# board.net
KiCad netlist of a schematic drawn in EAGLE
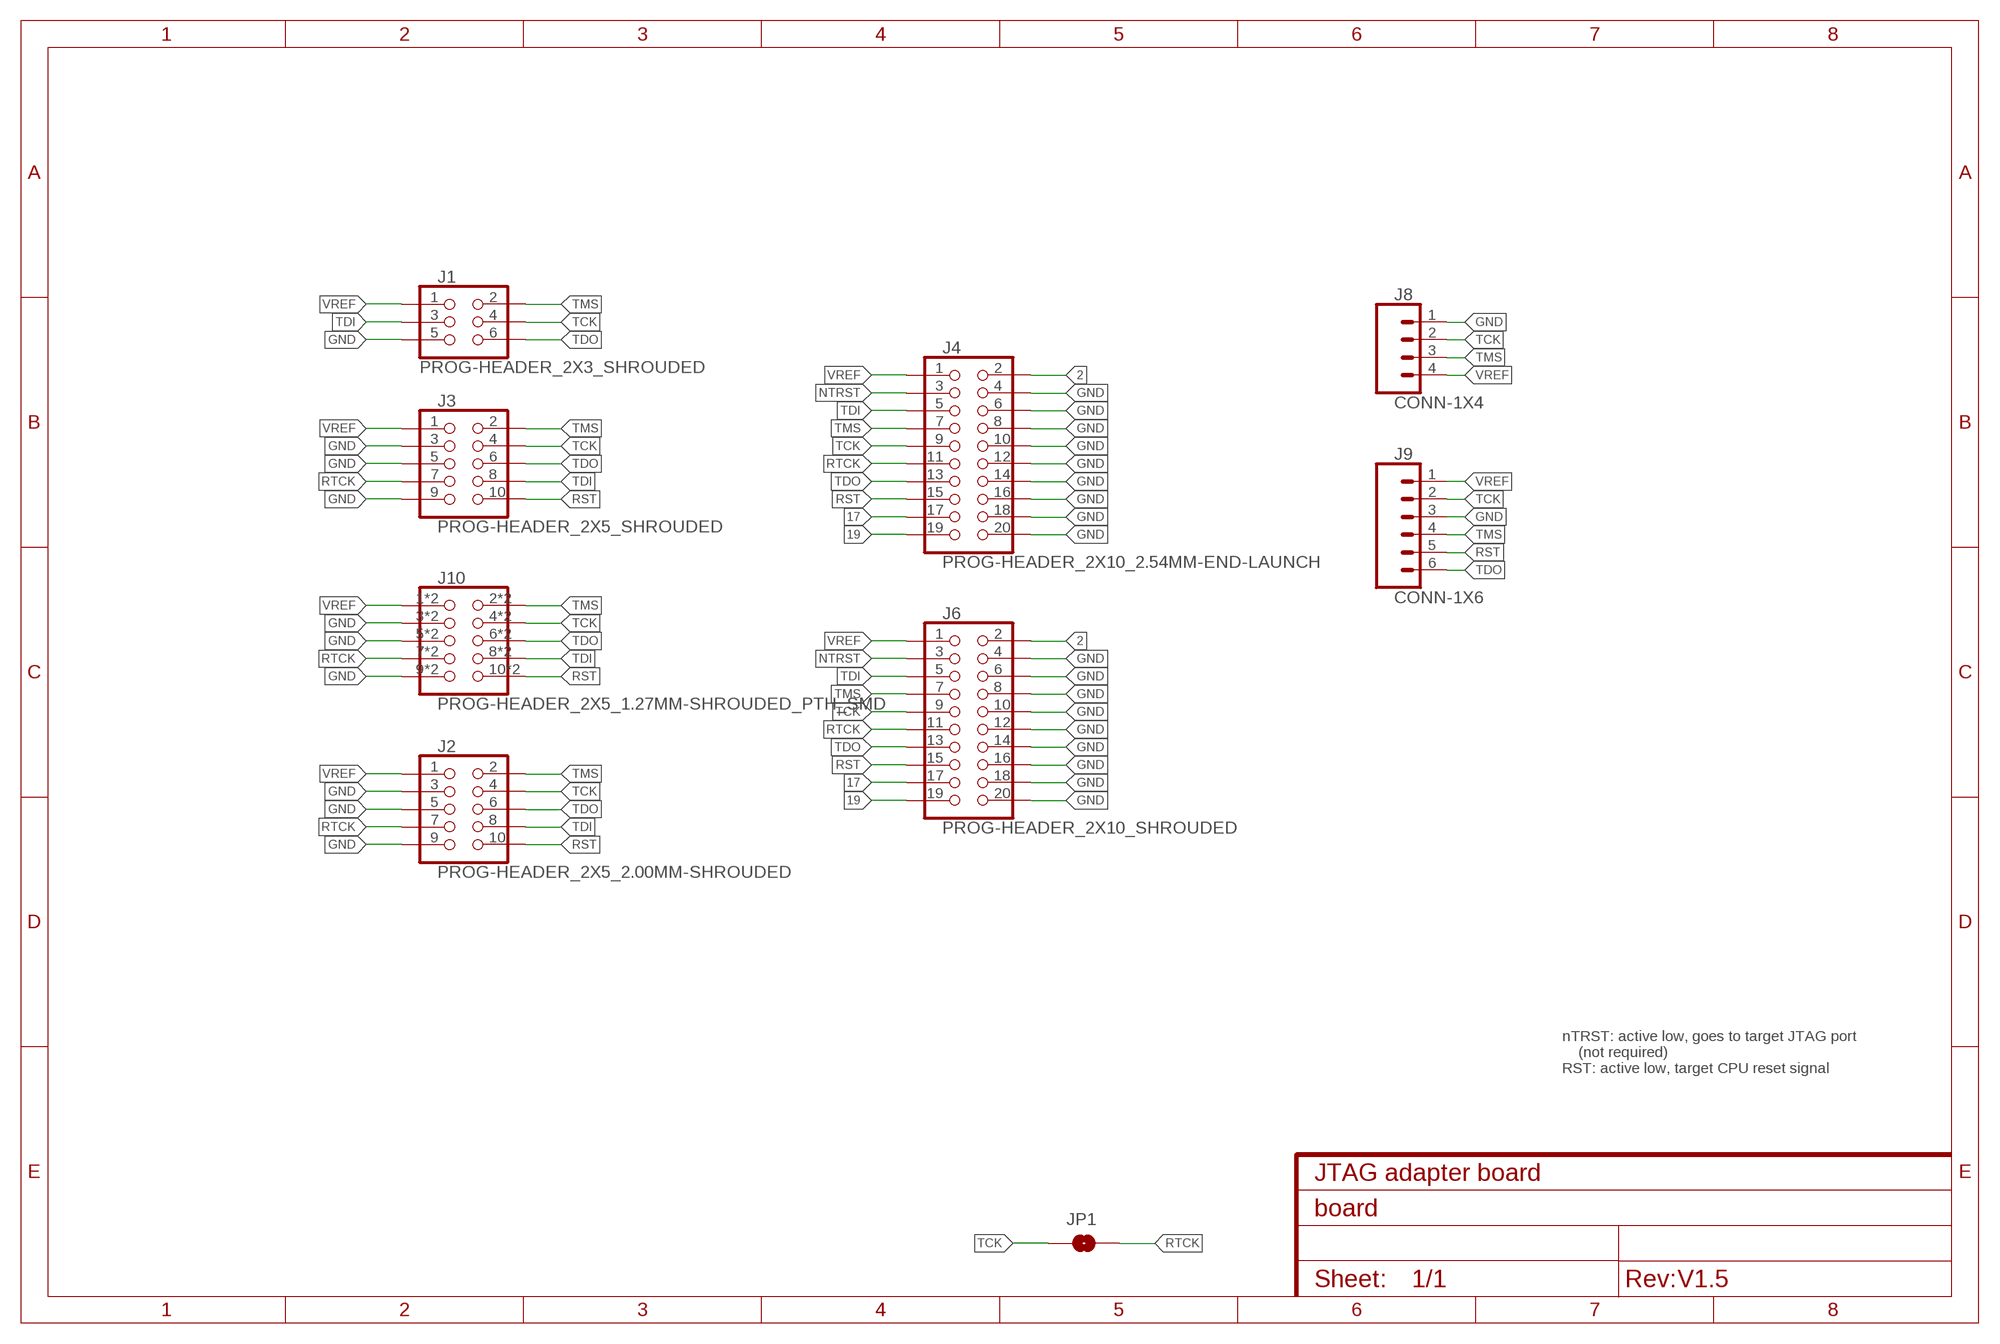
[diagram p0: schematic, sheet 1]

(export (version "E")
  (design (tool "Eeschema 10.0.6"))
  (components
    (comp (ref "J1")
      (value "PROG-HEADER_2X3_SHROUDED")
      (footprint "eagle-import:2X3-2.54MM-SHROUDED")
      (libsource (lib "eagle-import") (part "PROG-HEADER_2X3_SHROUDED"))
    )
    (comp (ref "J2")
      (value "PROG-HEADER_2X5_2.00MM-SHROUDED")
      (footprint "eagle-import:2X5-2.00MM-SHROUDED")
      (libsource (lib "eagle-import") (part "PROG-HEADER_2X5_2.00MM-SHROUDED"))
    )
    (comp (ref "J3")
      (value "PROG-HEADER_2X5_SHROUDED")
      (footprint "eagle-import:2X5-2.54MM-SHROUDED")
      (libsource (lib "eagle-import") (part "PROG-HEADER_2X5_SHROUDED"))
    )
    (comp (ref "J4")
      (value "PROG-HEADER_2X10_2.54MM-END-LAUNCH")
      (footprint "eagle-import:2X10-2.54MM-END-LAUNCH")
      (libsource (lib "eagle-import") (part "PROG-HEADER_2X10_2.54MM-END-LAUNCH"))
    )
    (comp (ref "J6")
      (value "PROG-HEADER_2X10_SHROUDED")
      (footprint "eagle-import:2X10-2.54MM-SHROUDED")
      (libsource (lib "eagle-import") (part "PROG-HEADER_2X10_SHROUDED"))
    )
    (comp (ref "J8")
      (value "CONN-1X4")
      (footprint "eagle-import:MOLEX-1X4-2.54MM")
      (libsource (lib "eagle-import") (part "CONN-1X4"))
    )
    (comp (ref "J9")
      (value "CONN-1X6")
      (footprint "eagle-import:MOLEX-1X6-2.54MM")
      (libsource (lib "eagle-import") (part "CONN-1X6"))
    )
    (comp (ref "J10")
      (value "PROG-HEADER_2X5_1.27MM-SHROUDED_PTH_SMD")
      (footprint "eagle-import:2X5-1.27MM-SHROUDED_PTH+SMD")
      (libsource (lib "eagle-import") (part "PROG-HEADER_2X5_1.27MM-SHROUDED_PTH_SMD"))
    )
    (comp (ref "JP1")
      (value "TCK-RTCK")
      (footprint "eagle-import:SMT-JUMPER_2_NO_SILK")
      (libsource (lib "eagle-import") (part "JUMPER-SMT_2_NO_SILK"))
    )
  )
  (nets
    (net (code "1") (name "2") (class "Default")
      (node (ref "J4") (pin "2") (pinfunction "2_2") (pintype "power_in"))
      (node (ref "J6") (pin "2") (pinfunction "2_2") (pintype "power_in"))
    )
    (net (code "2") (name "17") (class "Default")
      (node (ref "J4") (pin "17") (pinfunction "17_17") (pintype "passive"))
      (node (ref "J6") (pin "17") (pinfunction "17_17") (pintype "passive"))
    )
    (net (code "3") (name "19") (class "Default")
      (node (ref "J4") (pin "19") (pinfunction "19_19") (pintype "passive"))
      (node (ref "J6") (pin "19") (pinfunction "19_19") (pintype "passive"))
    )
    (net (code "4") (name "GND") (class "Default")
      (node (ref "J1") (pin "5") (pinfunction "5_5") (pintype "passive"))
      (node (ref "J10") (pin "13") (pinfunction "3_13") (pintype "passive"))
      (node (ref "J10") (pin "15") (pinfunction "5_15") (pintype "passive"))
      (node (ref "J10") (pin "19") (pinfunction "9_19") (pintype "passive"))
      (node (ref "J10") (pin "3") (pinfunction "3_3") (pintype "passive"))
      (node (ref "J10") (pin "5") (pinfunction "5_5") (pintype "passive"))
      (node (ref "J10") (pin "9") (pinfunction "9_9") (pintype "passive"))
      (node (ref "J2") (pin "3") (pinfunction "3_3") (pintype "passive"))
      (node (ref "J2") (pin "5") (pinfunction "5_5") (pintype "passive"))
      (node (ref "J2") (pin "9") (pinfunction "9_9") (pintype "passive"))
      (node (ref "J3") (pin "3") (pinfunction "3_3") (pintype "passive"))
      (node (ref "J3") (pin "5") (pinfunction "5_5") (pintype "passive"))
      (node (ref "J3") (pin "9") (pinfunction "9_9") (pintype "passive"))
      (node (ref "J4") (pin "10") (pinfunction "10_10") (pintype "power_in"))
      (node (ref "J4") (pin "12") (pinfunction "12_12") (pintype "power_in"))
      (node (ref "J4") (pin "14") (pinfunction "14_14") (pintype "power_in"))
      (node (ref "J4") (pin "16") (pinfunction "16_16") (pintype "power_in"))
      (node (ref "J4") (pin "18") (pinfunction "18_18") (pintype "power_in"))
      (node (ref "J4") (pin "20") (pinfunction "20_20") (pintype "power_in"))
      (node (ref "J4") (pin "4") (pinfunction "4_4") (pintype "power_in"))
      (node (ref "J4") (pin "6") (pinfunction "6_6") (pintype "power_in"))
      (node (ref "J4") (pin "8") (pinfunction "8_8") (pintype "power_in"))
      (node (ref "J6") (pin "10") (pinfunction "10_10") (pintype "power_in"))
      (node (ref "J6") (pin "12") (pinfunction "12_12") (pintype "power_in"))
      (node (ref "J6") (pin "14") (pinfunction "14_14") (pintype "power_in"))
      (node (ref "J6") (pin "16") (pinfunction "16_16") (pintype "power_in"))
      (node (ref "J6") (pin "18") (pinfunction "18_18") (pintype "power_in"))
      (node (ref "J6") (pin "20") (pinfunction "20_20") (pintype "power_in"))
      (node (ref "J6") (pin "4") (pinfunction "4_4") (pintype "power_in"))
      (node (ref "J6") (pin "6") (pinfunction "6_6") (pintype "power_in"))
      (node (ref "J6") (pin "8") (pinfunction "8_8") (pintype "power_in"))
      (node (ref "J8") (pin "1") (pinfunction "1_1") (pintype "passive"))
      (node (ref "J9") (pin "3") (pinfunction "3_3") (pintype "passive"))
    )
    (net (code "5") (name "NTRST") (class "Default")
      (node (ref "J4") (pin "3") (pinfunction "3_3") (pintype "passive"))
      (node (ref "J6") (pin "3") (pinfunction "3_3") (pintype "passive"))
    )
    (net (code "6") (name "RST") (class "Default")
      (node (ref "J10") (pin "10") (pinfunction "10_10") (pintype "power_in"))
      (node (ref "J10") (pin "20") (pinfunction "10_20") (pintype "power_in"))
      (node (ref "J2") (pin "10") (pinfunction "10_10") (pintype "power_in"))
      (node (ref "J3") (pin "10") (pinfunction "10_10") (pintype "power_in"))
      (node (ref "J4") (pin "15") (pinfunction "15_15") (pintype "passive"))
      (node (ref "J6") (pin "15") (pinfunction "15_15") (pintype "passive"))
      (node (ref "J9") (pin "5") (pinfunction "5_5") (pintype "passive"))
    )
    (net (code "7") (name "RTCK") (class "Default")
      (node (ref "J10") (pin "17") (pinfunction "7_17") (pintype "passive"))
      (node (ref "J10") (pin "7") (pinfunction "7_7") (pintype "passive"))
      (node (ref "J2") (pin "7") (pinfunction "7_7") (pintype "passive"))
      (node (ref "J3") (pin "7") (pinfunction "7_7") (pintype "passive"))
      (node (ref "J4") (pin "11") (pinfunction "11_11") (pintype "passive"))
      (node (ref "J6") (pin "11") (pinfunction "11_11") (pintype "passive"))
      (node (ref "JP1") (pin "2") (pinfunction "2_2") (pintype "passive"))
    )
    (net (code "8") (name "TCK") (class "Default")
      (node (ref "J1") (pin "4") (pinfunction "4_4") (pintype "passive"))
      (node (ref "J10") (pin "14") (pinfunction "4_14") (pintype "power_in"))
      (node (ref "J10") (pin "4") (pinfunction "4_4") (pintype "power_in"))
      (node (ref "J2") (pin "4") (pinfunction "4_4") (pintype "power_in"))
      (node (ref "J3") (pin "4") (pinfunction "4_4") (pintype "power_in"))
      (node (ref "J4") (pin "9") (pinfunction "9_9") (pintype "passive"))
      (node (ref "J6") (pin "9") (pinfunction "9_9") (pintype "passive"))
      (node (ref "J8") (pin "2") (pinfunction "2_2") (pintype "passive"))
      (node (ref "J9") (pin "2") (pinfunction "2_2") (pintype "passive"))
      (node (ref "JP1") (pin "1") (pinfunction "1_1") (pintype "passive"))
    )
    (net (code "9") (name "TDI") (class "Default")
      (node (ref "J1") (pin "3") (pinfunction "3_3") (pintype "passive"))
      (node (ref "J10") (pin "18") (pinfunction "8_18") (pintype "power_in"))
      (node (ref "J10") (pin "8") (pinfunction "8_8") (pintype "power_in"))
      (node (ref "J2") (pin "8") (pinfunction "8_8") (pintype "power_in"))
      (node (ref "J3") (pin "8") (pinfunction "8_8") (pintype "power_in"))
      (node (ref "J4") (pin "5") (pinfunction "5_5") (pintype "passive"))
      (node (ref "J6") (pin "5") (pinfunction "5_5") (pintype "passive"))
    )
    (net (code "10") (name "TDO") (class "Default")
      (node (ref "J1") (pin "6") (pinfunction "6_6") (pintype "passive"))
      (node (ref "J10") (pin "16") (pinfunction "6_16") (pintype "power_in"))
      (node (ref "J10") (pin "6") (pinfunction "6_6") (pintype "power_in"))
      (node (ref "J2") (pin "6") (pinfunction "6_6") (pintype "power_in"))
      (node (ref "J3") (pin "6") (pinfunction "6_6") (pintype "power_in"))
      (node (ref "J4") (pin "13") (pinfunction "13_13") (pintype "passive"))
      (node (ref "J6") (pin "13") (pinfunction "13_13") (pintype "passive"))
      (node (ref "J9") (pin "6") (pinfunction "6_6") (pintype "passive"))
    )
    (net (code "11") (name "TMS") (class "Default")
      (node (ref "J1") (pin "2") (pinfunction "2_2") (pintype "passive"))
      (node (ref "J10") (pin "12") (pinfunction "2_12") (pintype "power_in"))
      (node (ref "J10") (pin "2") (pinfunction "2_2") (pintype "power_in"))
      (node (ref "J2") (pin "2") (pinfunction "2_2") (pintype "power_in"))
      (node (ref "J3") (pin "2") (pinfunction "2_2") (pintype "power_in"))
      (node (ref "J4") (pin "7") (pinfunction "7_7") (pintype "passive"))
      (node (ref "J6") (pin "7") (pinfunction "7_7") (pintype "passive"))
      (node (ref "J8") (pin "3") (pinfunction "3_3") (pintype "passive"))
      (node (ref "J9") (pin "4") (pinfunction "4_4") (pintype "passive"))
    )
    (net (code "12") (name "VREF") (class "Default")
      (node (ref "J1") (pin "1") (pinfunction "1_1") (pintype "passive"))
      (node (ref "J10") (pin "1") (pinfunction "1_1") (pintype "passive"))
      (node (ref "J10") (pin "11") (pinfunction "1_11") (pintype "passive"))
      (node (ref "J2") (pin "1") (pinfunction "1_1") (pintype "passive"))
      (node (ref "J3") (pin "1") (pinfunction "1_1") (pintype "passive"))
      (node (ref "J4") (pin "1") (pinfunction "1_1") (pintype "passive"))
      (node (ref "J6") (pin "1") (pinfunction "1_1") (pintype "passive"))
      (node (ref "J8") (pin "4") (pinfunction "4_4") (pintype "passive"))
      (node (ref "J9") (pin "1") (pinfunction "1_1") (pintype "passive"))
    )
  )
)
